# Irradiance_Sensor.net
KiCad netlist of a schematic drawn in Altium Designer
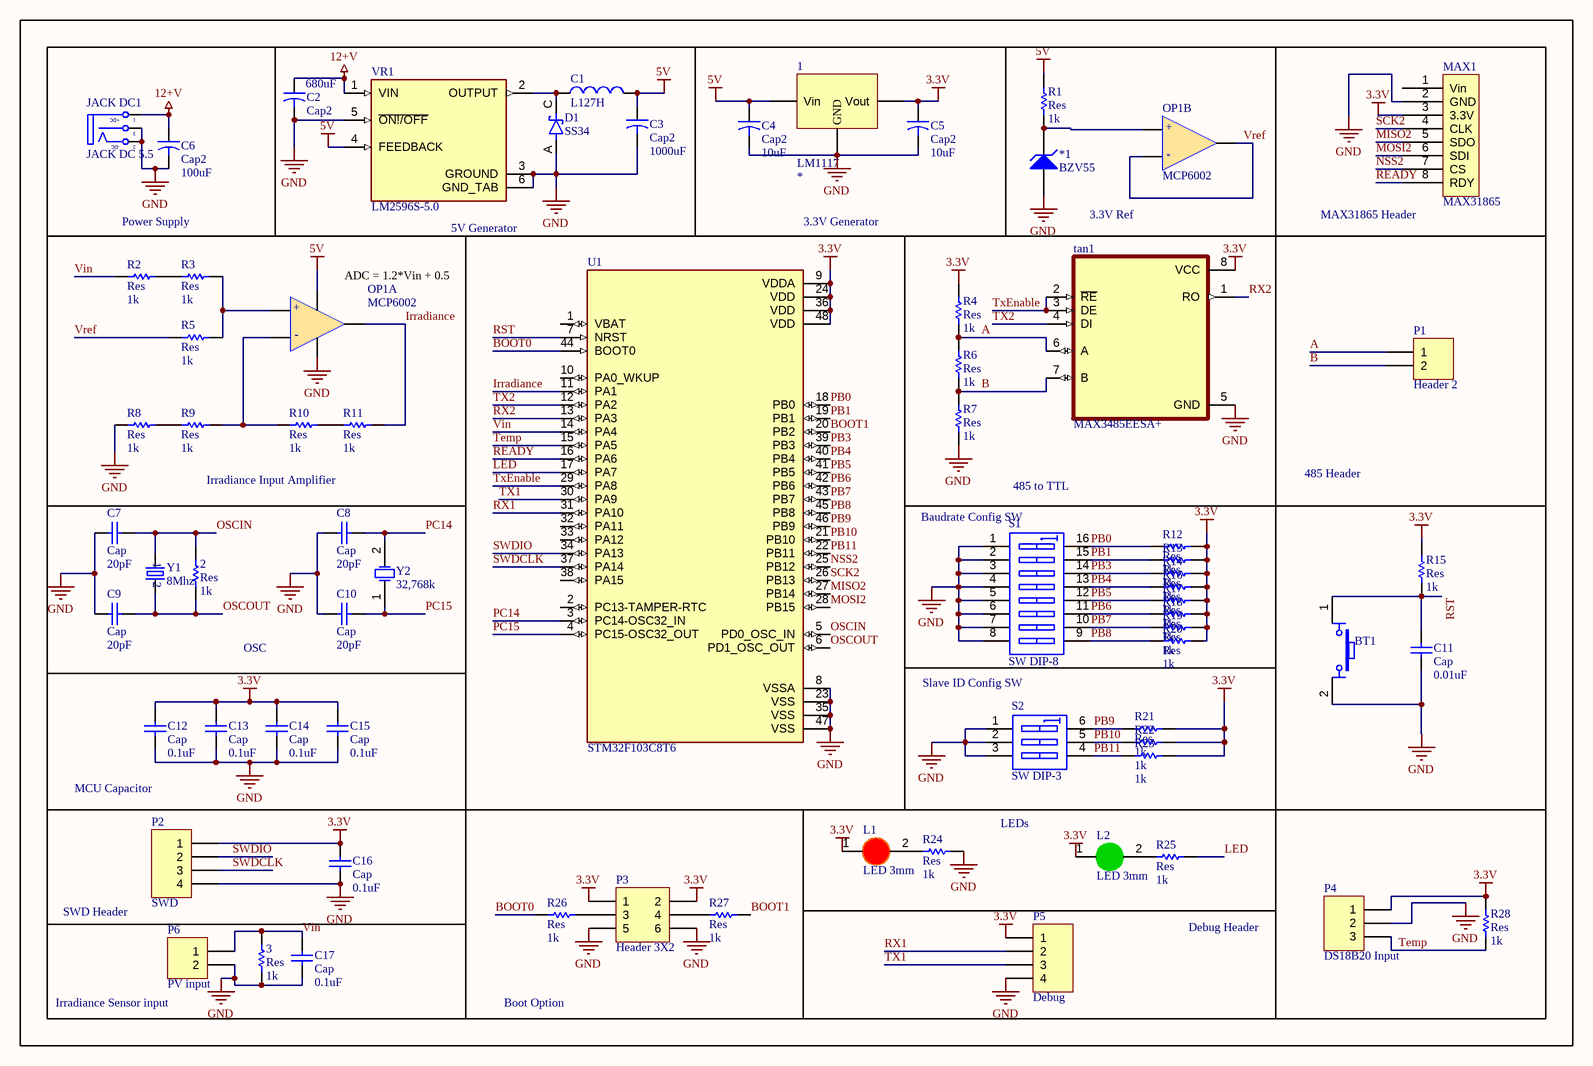
[diagram p0: Irradiance Sensor.SchDoc]

(export (version "E")
  (design (tool "Eeschema 10.0.6"))
  (components
    (comp (ref "*1") (value "BZV55") (footprint "SOD-80C") (libsource (lib "Miles") (part "BZV55")))
    (comp (ref "1")
      (value "LM1117")
      (footprint "SOT230P700X180-4N")
      (fields (field (name "VOLTAGE") "*"))
      (libsource (lib "Miles") (part "LM1117"))
    )
    (comp (ref "2")
      (value "Res")
      (footprint "RESC2012X11N")
      (fields (field (name "ALTIUM_VALUE") "1k"))
      (libsource (lib "Miles") (part "Res"))
    )
    (comp (ref "3")
      (value "Res")
      (footprint "RESC2012X11N")
      (fields (field (name "ALTIUM_VALUE") "1k"))
      (libsource (lib "Miles") (part "Res"))
    )
    (comp (ref "BT1")
      (value "Nut Nhan 4 Chan Cam 6x6")
      (footprint "Nut Nhan 4 Chan Cam 6x6")
      (description "Nut Nhan 4 Chan 6x6mm")
      (libsource (lib "Altium_Lib_by_KhueNguyenCreator") (part "Nut Nhan 4 Chan Cam 6x6"))
    )
    (comp (ref "C1") (value "L127H") (footprint "INDP122122X80N") (libsource (lib "Miles") (part "L127H")))
    (comp (ref "C2")
      (value "Cap2")
      (footprint "CAPR5-4X5")
      (description "Capacitor")
      (fields (field (name "ALTIUM_VALUE") "680uF") (field (name "PUBLISHER") "Altium Limited"))
      (libsource (lib "Miscellaneous Devices") (part "Cap2"))
    )
    (comp (ref "C3")
      (value "Cap2")
      (footprint "CAPR5-4X5")
      (description "Capacitor")
      (fields (field (name "ALTIUM_VALUE") "1000uF") (field (name "PUBLISHER") "Altium Limited"))
      (libsource (lib "Miscellaneous Devices") (part "Cap2"))
    )
    (comp (ref "C4")
      (value "Cap2")
      (footprint "CAPR5-4X5")
      (description "Capacitor")
      (fields (field (name "ALTIUM_VALUE") "10uF") (field (name "PUBLISHER") "Altium Limited"))
      (libsource (lib "Miscellaneous Devices") (part "Cap2"))
    )
    (comp (ref "C5")
      (value "Cap2")
      (footprint "CAPR5-4X5")
      (description "Capacitor")
      (fields (field (name "ALTIUM_VALUE") "10uF") (field (name "PUBLISHER") "Altium Limited"))
      (libsource (lib "Miscellaneous Devices") (part "Cap2"))
    )
    (comp (ref "C6")
      (value "Cap2")
      (footprint "CAPR5-4X5")
      (description "Capacitor")
      (fields (field (name "ALTIUM_VALUE") "100uF") (field (name "PUBLISHER") "Altium Limited"))
      (libsource (lib "Miscellaneous Devices") (part "Cap2"))
    )
    (comp (ref "C7")
      (value "Cap")
      (footprint "RESC2012X11N")
      (fields (field (name "CAP") "20pF"))
      (libsource (lib "Miles") (part "Cap"))
    )
    (comp (ref "C8")
      (value "Cap")
      (footprint "RESC2012X11N")
      (fields (field (name "CAP") "20pF"))
      (libsource (lib "Miles") (part "Cap"))
    )
    (comp (ref "C9")
      (value "Cap")
      (footprint "RESC2012X11N")
      (fields (field (name "CAP") "20pF"))
      (libsource (lib "Miles") (part "Cap"))
    )
    (comp (ref "C10")
      (value "Cap")
      (footprint "RESC2012X11N")
      (fields (field (name "CAP") "20pF"))
      (libsource (lib "Miles") (part "Cap"))
    )
    (comp (ref "C11")
      (value "Cap")
      (footprint "RESC2012X11N")
      (fields (field (name "CAP") "0.01uF"))
      (libsource (lib "Miles") (part "Cap"))
    )
    (comp (ref "C12")
      (value "Cap")
      (footprint "RESC2012X11N")
      (fields (field (name "CAP") "0.1uF"))
      (libsource (lib "Miles") (part "Cap"))
    )
    (comp (ref "C13")
      (value "Cap")
      (footprint "RESC2012X11N")
      (fields (field (name "CAP") "0.1uF"))
      (libsource (lib "Miles") (part "Cap"))
    )
    (comp (ref "C14")
      (value "Cap")
      (footprint "RESC2012X11N")
      (fields (field (name "CAP") "0.1uF"))
      (libsource (lib "Miles") (part "Cap"))
    )
    (comp (ref "C15")
      (value "Cap")
      (footprint "RESC2012X11N")
      (fields (field (name "CAP") "0.1uF"))
      (libsource (lib "Miles") (part "Cap"))
    )
    (comp (ref "C16")
      (value "Cap")
      (footprint "RESC2012X11N")
      (fields (field (name "CAP") "0.1uF"))
      (libsource (lib "Miles") (part "Cap"))
    )
    (comp (ref "C17")
      (value "Cap")
      (footprint "RESC2012X11N")
      (fields (field (name "CAP") "0.1uF"))
      (libsource (lib "Miles") (part "Cap"))
    )
    (comp (ref "D1")
      (value "SS34")
      (footprint "DIOM7959X265N")
      (description "Diode Schottky 40V 3A Surface Mount SMC _DO-214AB_")
      (fields (field (name "MF") "ON Semiconductor"))
      (libsource (lib "SS34") (part "SS34"))
    )
    (comp (ref "JACK DC1")
      (value "JACK DC 5.5")
      (footprint "JACK DC 5.5")
      (libsource (lib "Altium_Lib_by_KhueNguyenCreator") (part "JACK DC 5.5"))
    )
    (comp (ref "L1")
      (value "LED 3mm")
      (footprint "LED-3MM-RED")
      (description "Cắm")
      (libsource (lib "Altium_Lib_by_KhueNguyenCreator") (part "LED 3mm Do"))
    )
    (comp (ref "L2")
      (value "LED 3mm")
      (footprint "LED-3MM-GREEN")
      (description "Cắm")
      (libsource (lib "Altium_Lib_by_KhueNguyenCreator") (part "LED 3mm Xanh La"))
    )
    (comp (ref "MAX1") (value "MAX31865") (footprint "MAX31865") (libsource (lib "Miles") (part "MAX31865")))
    (comp (ref "OP1") (value "MCP6002") (footprint "DIP8") (libsource (lib "Miles") (part "MCP6002")))
    (comp (ref "P1")
      (value "Header 2")
      (footprint "TE_282837-2")
      (description "Header, 2-Pin")
      (fields (field (name "PUBLISHER") "Altium Limited"))
      (libsource (lib "Miscellaneous Connectors") (part "Header 2"))
    )
    (comp (ref "P2")
      (value "SWD")
      (footprint "HDR1X4")
      (description "Header, 4-Pin")
      (fields (field (name "PUBLISHER") "Altium Limited"))
      (libsource (lib "Miscellaneous Connectors") (part "Header 4"))
    )
    (comp (ref "P3")
      (value "Header 3X2")
      (footprint "HDR2X3")
      (description "Header, 3-Pin, Dual row")
      (fields (field (name "PUBLISHER") "Altium Limited"))
      (libsource (lib "Miscellaneous Connectors") (part "Header 3X2"))
    )
    (comp (ref "P4")
      (value "DS18B20 Input")
      (footprint "HDR1X3")
      (description "Header, 3-Pin")
      (fields (field (name "PUBLISHER") "Altium Limited"))
      (libsource (lib "Miscellaneous Connectors") (part "Header 3"))
    )
    (comp (ref "P5")
      (value "Debug")
      (footprint "HDR1X4")
      (description "Header, 4-Pin")
      (fields (field (name "PUBLISHER") "Altium Limited"))
      (libsource (lib "") (part "Header 4_1"))
    )
    (comp (ref "P6")
      (value "PV input")
      (footprint "HDR1X2")
      (description "Header, 2-Pin")
      (fields (field (name "PUBLISHER") "Altium Limited"))
      (libsource (lib "") (part "Header 2_1"))
    )
    (comp (ref "R1")
      (value "Res")
      (footprint "RESC2012X11N")
      (fields (field (name "ALTIUM_VALUE") "1k"))
      (libsource (lib "Miles") (part "Res"))
    )
    (comp (ref "R2")
      (value "Res")
      (footprint "RESC2012X11N")
      (fields (field (name "ALTIUM_VALUE") "1k"))
      (libsource (lib "Miles") (part "Res"))
    )
    (comp (ref "R3")
      (value "Res")
      (footprint "RESC2012X11N")
      (fields (field (name "ALTIUM_VALUE") "1k"))
      (libsource (lib "Miles") (part "Res"))
    )
    (comp (ref "R4")
      (value "Res")
      (footprint "RESC2012X11N")
      (fields (field (name "ALTIUM_VALUE") "1k"))
      (libsource (lib "Miles") (part "Res"))
    )
    (comp (ref "R5")
      (value "Res")
      (footprint "RESC2012X11N")
      (fields (field (name "ALTIUM_VALUE") "1k"))
      (libsource (lib "Miles") (part "Res"))
    )
    (comp (ref "R6")
      (value "Res")
      (footprint "RESC2012X11N")
      (fields (field (name "ALTIUM_VALUE") "1k"))
      (libsource (lib "Miles") (part "Res"))
    )
    (comp (ref "R7")
      (value "Res")
      (footprint "RESC2012X11N")
      (fields (field (name "ALTIUM_VALUE") "1k"))
      (libsource (lib "Miles") (part "Res"))
    )
    (comp (ref "R8")
      (value "Res")
      (footprint "RESC2012X11N")
      (fields (field (name "ALTIUM_VALUE") "1k"))
      (libsource (lib "Miles") (part "Res"))
    )
    (comp (ref "R9")
      (value "Res")
      (footprint "RESC2012X11N")
      (fields (field (name "ALTIUM_VALUE") "1k"))
      (libsource (lib "Miles") (part "Res"))
    )
    (comp (ref "R10")
      (value "Res")
      (footprint "RESC2012X11N")
      (fields (field (name "ALTIUM_VALUE") "1k"))
      (libsource (lib "Miles") (part "Res"))
    )
    (comp (ref "R11")
      (value "Res")
      (footprint "RESC2012X11N")
      (fields (field (name "ALTIUM_VALUE") "1k"))
      (libsource (lib "Miles") (part "Res"))
    )
    (comp (ref "R12")
      (value "Res")
      (footprint "RESC2012X11N")
      (fields (field (name "ALTIUM_VALUE") "1k"))
      (libsource (lib "Miles") (part "Res"))
    )
    (comp (ref "R13")
      (value "Res")
      (footprint "RESC2012X11N")
      (fields (field (name "ALTIUM_VALUE") "1k"))
      (libsource (lib "Miles") (part "Res"))
    )
    (comp (ref "R14")
      (value "Res")
      (footprint "RESC2012X11N")
      (fields (field (name "ALTIUM_VALUE") "1k"))
      (libsource (lib "Miles") (part "Res"))
    )
    (comp (ref "R15")
      (value "Res")
      (footprint "RESC2012X11N")
      (fields (field (name "ALTIUM_VALUE") "1k"))
      (libsource (lib "Miles") (part "Res"))
    )
    (comp (ref "R16")
      (value "Res")
      (footprint "RESC2012X11N")
      (fields (field (name "ALTIUM_VALUE") "1k"))
      (libsource (lib "Miles") (part "Res"))
    )
    (comp (ref "R17")
      (value "Res")
      (footprint "RESC2012X11N")
      (fields (field (name "ALTIUM_VALUE") "1k"))
      (libsource (lib "Miles") (part "Res"))
    )
    (comp (ref "R18")
      (value "Res")
      (footprint "RESC2012X11N")
      (fields (field (name "ALTIUM_VALUE") "1k"))
      (libsource (lib "Miles") (part "Res"))
    )
    (comp (ref "R19")
      (value "Res")
      (footprint "RESC2012X11N")
      (fields (field (name "ALTIUM_VALUE") "1k"))
      (libsource (lib "Miles") (part "Res"))
    )
    (comp (ref "R20")
      (value "Res")
      (footprint "RESC2012X11N")
      (fields (field (name "ALTIUM_VALUE") "1k"))
      (libsource (lib "Miles") (part "Res"))
    )
    (comp (ref "R21")
      (value "Res")
      (footprint "RESC2012X11N")
      (fields (field (name "ALTIUM_VALUE") "1k"))
      (libsource (lib "Miles") (part "Res"))
    )
    (comp (ref "R22") (value "1k") (footprint "RESC2012X11N") (libsource (lib "Miles") (part "Res")))
    (comp (ref "R23") (value "1k") (footprint "RESC2012X11N") (libsource (lib "Miles") (part "Res")))
    (comp (ref "R24")
      (value "Res")
      (footprint "RESC2012X11N")
      (fields (field (name "ALTIUM_VALUE") "1k"))
      (libsource (lib "Miles") (part "Res"))
    )
    (comp (ref "R25")
      (value "Res")
      (footprint "RESC2012X11N")
      (fields (field (name "ALTIUM_VALUE") "1k"))
      (libsource (lib "Miles") (part "Res"))
    )
    (comp (ref "R26")
      (value "Res")
      (footprint "RESC2012X11N")
      (fields (field (name "ALTIUM_VALUE") "1k"))
      (libsource (lib "Miles") (part "Res"))
    )
    (comp (ref "R27")
      (value "Res")
      (footprint "RESC2012X11N")
      (fields (field (name "ALTIUM_VALUE") "1k"))
      (libsource (lib "Miles") (part "Res"))
    )
    (comp (ref "R28")
      (value "Res")
      (footprint "RESC2012X11N")
      (fields (field (name "ALTIUM_VALUE") "1k"))
      (libsource (lib "Miles") (part "Res"))
    )
    (comp (ref "S1")
      (value "SW DIP-8")
      (footprint "DIP16")
      (description "DIP Switch, 8 Position, SPST")
      (fields (field (name "PUBLISHER") "Altium Limited"))
      (libsource (lib "Miscellaneous Devices") (part "SW DIP-8"))
    )
    (comp (ref "S2")
      (value "SW DIP-3")
      (footprint "DIP-6")
      (description "DIP Switch, 3 Position, SPST")
      (fields (field (name "PUBLISHER") "Altium Limited"))
      (libsource (lib "Miscellaneous Devices") (part "SW DIP-3"))
    )
    (comp (ref "tan1")
      (value "MAX3485EESA+")
      (footprint "SOIC127P600X175-8N")
      (description "1/1 Transceiver Half RS422, RS485 8-SOIC")
      (fields (field (name "MF") "Maxim Integrated"))
      (libsource (lib "MAX3485EESA_") (part "MAX3485EESA+"))
    )
    (comp (ref "U1")
      (value "STM32F103C8T6")
      (footprint "QFP50P900X900X160-48N")
      (description "ARMÂ® CortexÂ®-M3 STM32F1 Microcontroller IC 32-Bit 72MHz 64KB _64K x 8_ FLASH")
      (fields (field (name "MF") "STMicroelectronics"))
      (libsource (lib "STM32F103C8T6") (part "STM32F103C8T6"))
    )
    (comp (ref "VR1")
      (value "LM2596S-5.0")
      (footprint "TO170P1524X483-6N")
      (description "SIMPLE SWITCHER&reg; 4.5V to 40V, 3A Low Component Count Step-Down Regulator 5-DDPAK/TO-263")
      (fields (field (name "MF") "Texas Instruments") (field (name "MP") "LM2596S-5.0/NOPB"))
      (libsource (lib "LM2596S-5.0") (part "LM2596S-5.0"))
    )
    (comp (ref "Y1")
      (value "8Mhz")
      (footprint "HC49US")
      (description "DIP Crystal 8MHz-20pF-20ppm-60R;")
      (fields (field (name "MF") "Xinhunjing") (field (name "MP") "49S8M"))
      (libsource (lib "DIP-CRYSTAL-8MHZ-20PF-20PPM-60R_HC49US_") (part "DIP-CRYSTAL-8MHZ-20PF-20PPM-60R(HC49US)"))
    )
    (comp (ref "Y2")
      (value "32,768k")
      (footprint "R38")
      (description "Crystal Oscillator")
      (fields (field (name "PUBLISHER") "Altium Limited"))
      (libsource (lib "Miscellaneous Devices") (part "XTAL"))
    )
  )
  (nets
    (net (code "1") (name "/A") (class "Default")
      (node (ref "P1") (pin "1") (pinfunction "1_1") (pintype "passive"))
      (node (ref "R4") (pin "1") (pinfunction "1_1") (pintype "passive"))
      (node (ref "R6") (pin "2") (pinfunction "2_2") (pintype "passive"))
      (node (ref "tan1") (pin "6") (pinfunction "A_6") (pintype "bidirectional"))
    )
    (net (code "2") (name "/B") (class "Default")
      (node (ref "P1") (pin "2") (pinfunction "2_2") (pintype "passive"))
      (node (ref "R6") (pin "1") (pinfunction "1_1") (pintype "passive"))
      (node (ref "R7") (pin "2") (pinfunction "2_2") (pintype "passive"))
      (node (ref "tan1") (pin "7") (pinfunction "B_7") (pintype "bidirectional"))
    )
    (net (code "3") (name "/BOOT0") (class "Default")
      (node (ref "R26") (pin "2") (pinfunction "2_2") (pintype "passive"))
      (node (ref "U1") (pin "44") (pinfunction "BOOT0_44") (pintype "input"))
    )
    (net (code "4") (name "/BOOT1") (class "Default")
      (node (ref "R27") (pin "1") (pinfunction "1_1") (pintype "passive"))
      (node (ref "U1") (pin "20") (pinfunction "PB2_20") (pintype "bidirectional"))
    )
    (net (code "5") (name "/Irradiance") (class "Default")
      (node (ref "OP1") (pin "1") (pinfunction "VoutA_1") (pintype "passive"))
      (node (ref "R11") (pin "2") (pinfunction "2_2") (pintype "passive"))
      (node (ref "U1") (pin "11") (pinfunction "PA1_11") (pintype "bidirectional"))
    )
    (net (code "6") (name "/LED") (class "Default")
      (node (ref "R25") (pin "1") (pinfunction "1_1") (pintype "passive"))
      (node (ref "U1") (pin "17") (pinfunction "PA7_17") (pintype "bidirectional"))
    )
    (net (code "7") (name "/MISO2") (class "Default")
      (node (ref "MAX1") (pin "5") (pinfunction "SDO_5") (pintype "passive"))
      (node (ref "U1") (pin "27") (pinfunction "PB14_27") (pintype "bidirectional"))
    )
    (net (code "8") (name "/MOSI2") (class "Default")
      (node (ref "MAX1") (pin "6") (pinfunction "SDI_6") (pintype "passive"))
      (node (ref "U1") (pin "28") (pinfunction "PB15_28") (pintype "bidirectional"))
    )
    (net (code "9") (name "/NSS2") (class "Default")
      (node (ref "MAX1") (pin "7") (pinfunction "CS_7") (pintype "passive"))
      (node (ref "U1") (pin "25") (pinfunction "PB12_25") (pintype "bidirectional"))
    )
    (net (code "10") (name "/OSCIN") (class "Default")
      (node (ref "2") (pin "2") (pinfunction "2_2") (pintype "passive"))
      (node (ref "C7") (pin "2") (pinfunction "2_2") (pintype "passive"))
      (node (ref "U1") (pin "5") (pinfunction "PD0_OSC_IN_5") (pintype "bidirectional"))
      (node (ref "Y1") (pin "1") (pinfunction "1_1") (pintype "passive"))
    )
    (net (code "11") (name "/OSCOUT") (class "Default")
      (node (ref "2") (pin "1") (pinfunction "1_1") (pintype "passive"))
      (node (ref "C9") (pin "2") (pinfunction "2_2") (pintype "passive"))
      (node (ref "U1") (pin "6") (pinfunction "PD1_OSC_OUT_6") (pintype "bidirectional"))
      (node (ref "Y1") (pin "2") (pinfunction "2_2") (pintype "passive"))
    )
    (net (code "12") (name "/PB0") (class "Default")
      (node (ref "R12") (pin "2") (pinfunction "2_2") (pintype "passive"))
      (node (ref "S1") (pin "16") (pinfunction "B1_16") (pintype "passive"))
      (node (ref "U1") (pin "18") (pinfunction "PB0_18") (pintype "bidirectional"))
    )
    (net (code "13") (name "/PB1") (class "Default")
      (node (ref "R13") (pin "2") (pinfunction "2_2") (pintype "passive"))
      (node (ref "S1") (pin "15") (pinfunction "B2_15") (pintype "passive"))
      (node (ref "U1") (pin "19") (pinfunction "PB1_19") (pintype "bidirectional"))
    )
    (net (code "14") (name "/PB3") (class "Default")
      (node (ref "R14") (pin "2") (pinfunction "2_2") (pintype "passive"))
      (node (ref "S1") (pin "14") (pinfunction "B3_14") (pintype "passive"))
      (node (ref "U1") (pin "39") (pinfunction "PB3_39") (pintype "bidirectional"))
    )
    (net (code "15") (name "/PB4") (class "Default")
      (node (ref "R16") (pin "2") (pinfunction "2_2") (pintype "passive"))
      (node (ref "S1") (pin "13") (pinfunction "B4_13") (pintype "passive"))
      (node (ref "U1") (pin "40") (pinfunction "PB4_40") (pintype "bidirectional"))
    )
    (net (code "16") (name "/PB5") (class "Default")
      (node (ref "R17") (pin "2") (pinfunction "2_2") (pintype "passive"))
      (node (ref "S1") (pin "12") (pinfunction "B5_12") (pintype "passive"))
      (node (ref "U1") (pin "41") (pinfunction "PB5_41") (pintype "bidirectional"))
    )
    (net (code "17") (name "/PB6") (class "Default")
      (node (ref "R18") (pin "2") (pinfunction "2_2") (pintype "passive"))
      (node (ref "S1") (pin "11") (pinfunction "B6_11") (pintype "passive"))
      (node (ref "U1") (pin "42") (pinfunction "PB6_42") (pintype "bidirectional"))
    )
    (net (code "18") (name "/PB7") (class "Default")
      (node (ref "R19") (pin "2") (pinfunction "2_2") (pintype "passive"))
      (node (ref "S1") (pin "10") (pinfunction "B7_10") (pintype "passive"))
      (node (ref "U1") (pin "43") (pinfunction "PB7_43") (pintype "bidirectional"))
    )
    (net (code "19") (name "/PB8") (class "Default")
      (node (ref "R20") (pin "2") (pinfunction "2_2") (pintype "passive"))
      (node (ref "S1") (pin "9") (pinfunction "B8_9") (pintype "passive"))
      (node (ref "U1") (pin "45") (pinfunction "PB8_45") (pintype "bidirectional"))
    )
    (net (code "20") (name "/PB9") (class "Default")
      (node (ref "R21") (pin "2") (pinfunction "2_2") (pintype "passive"))
      (node (ref "S2") (pin "6") (pinfunction "B1_6") (pintype "passive"))
      (node (ref "U1") (pin "46") (pinfunction "PB9_46") (pintype "bidirectional"))
    )
    (net (code "21") (name "/PB10") (class "Default")
      (node (ref "R22") (pin "2") (pinfunction "2_2") (pintype "passive"))
      (node (ref "S2") (pin "5") (pinfunction "B2_5") (pintype "passive"))
      (node (ref "U1") (pin "21") (pinfunction "PB10_21") (pintype "bidirectional"))
    )
    (net (code "22") (name "/PB11") (class "Default")
      (node (ref "R23") (pin "2") (pinfunction "2_2") (pintype "passive"))
      (node (ref "S2") (pin "4") (pinfunction "B3_4") (pintype "passive"))
      (node (ref "U1") (pin "22") (pinfunction "PB11_22") (pintype "bidirectional"))
    )
    (net (code "23") (name "/PC14") (class "Default")
      (node (ref "C8") (pin "2") (pinfunction "2_2") (pintype "passive"))
      (node (ref "U1") (pin "3") (pinfunction "PC14-OSC32_IN_3") (pintype "bidirectional"))
      (node (ref "Y2") (pin "2") (pinfunction "OSC2_2") (pintype "passive"))
    )
    (net (code "24") (name "/PC15") (class "Default")
      (node (ref "C10") (pin "2") (pinfunction "2_2") (pintype "passive"))
      (node (ref "U1") (pin "4") (pinfunction "PC15-OSC32_OUT_4") (pintype "bidirectional"))
      (node (ref "Y2") (pin "1") (pinfunction "OSC1_1") (pintype "passive"))
    )
    (net (code "25") (name "/READY") (class "Default")
      (node (ref "MAX1") (pin "8") (pinfunction "RDY_8") (pintype "passive"))
      (node (ref "U1") (pin "16") (pinfunction "PA6_16") (pintype "bidirectional"))
    )
    (net (code "26") (name "/RST") (class "Default")
      (node (ref "BT1") (pin "1") (pintype "passive"))
      (node (ref "C11") (pin "1") (pinfunction "1_1") (pintype "passive"))
      (node (ref "R15") (pin "1") (pinfunction "1_1") (pintype "passive"))
      (node (ref "U1") (pin "7") (pinfunction "NRST_7") (pintype "input"))
    )
    (net (code "27") (name "/RX1") (class "Default")
      (node (ref "P5") (pin "2") (pinfunction "2_2") (pintype "passive"))
      (node (ref "U1") (pin "31") (pinfunction "PA10_31") (pintype "bidirectional"))
    )
    (net (code "28") (name "/RX2") (class "Default")
      (node (ref "U1") (pin "13") (pinfunction "PA3_13") (pintype "bidirectional"))
      (node (ref "tan1") (pin "1") (pinfunction "RO_1") (pintype "output"))
    )
    (net (code "29") (name "/SCK2") (class "Default")
      (node (ref "MAX1") (pin "4") (pinfunction "CLK_4") (pintype "passive"))
      (node (ref "U1") (pin "26") (pinfunction "PB13_26") (pintype "bidirectional"))
    )
    (net (code "30") (name "/SWDCLK") (class "Default")
      (node (ref "P2") (pin "3") (pinfunction "3_3") (pintype "passive"))
      (node (ref "U1") (pin "37") (pinfunction "PA14_37") (pintype "bidirectional"))
    )
    (net (code "31") (name "/SWDIO") (class "Default")
      (node (ref "P2") (pin "2") (pinfunction "2_2") (pintype "passive"))
      (node (ref "U1") (pin "34") (pinfunction "PA13_34") (pintype "bidirectional"))
    )
    (net (code "32") (name "/TX1") (class "Default")
      (node (ref "P5") (pin "3") (pinfunction "3_3") (pintype "passive"))
      (node (ref "U1") (pin "30") (pinfunction "PA9_30") (pintype "bidirectional"))
    )
    (net (code "33") (name "/TX2") (class "Default")
      (node (ref "U1") (pin "12") (pinfunction "PA2_12") (pintype "bidirectional"))
      (node (ref "tan1") (pin "4") (pinfunction "DI_4") (pintype "input"))
    )
    (net (code "34") (name "/Temp") (class "Default")
      (node (ref "P4") (pin "3") (pinfunction "3_3") (pintype "passive"))
      (node (ref "R28") (pin "1") (pinfunction "1_1") (pintype "passive"))
      (node (ref "U1") (pin "15") (pinfunction "PA5_15") (pintype "bidirectional"))
    )
    (net (code "35") (name "/TxEnable") (class "Default")
      (node (ref "U1") (pin "29") (pinfunction "PA8_29") (pintype "bidirectional"))
      (node (ref "tan1") (pin "2") (pinfunction "~{RE}_2") (pintype "input"))
      (node (ref "tan1") (pin "3") (pinfunction "DE_3") (pintype "input"))
    )
    (net (code "36") (name "/Vin") (class "Default")
      (node (ref "3") (pin "2") (pinfunction "2_2") (pintype "passive"))
      (node (ref "C17") (pin "1") (pinfunction "1_1") (pintype "passive"))
      (node (ref "P6") (pin "1") (pinfunction "1_1") (pintype "passive"))
      (node (ref "R2") (pin "1") (pinfunction "1_1") (pintype "passive"))
      (node (ref "U1") (pin "14") (pinfunction "PA4_14") (pintype "bidirectional"))
    )
    (net (code "37") (name "/Vref") (class "Default")
      (node (ref "OP1") (pin "6") (pinfunction "Vinb-_6") (pintype "passive"))
      (node (ref "OP1") (pin "7") (pinfunction "VoutB_7") (pintype "passive"))
      (node (ref "R5") (pin "1") (pinfunction "1_1") (pintype "passive"))
    )
    (net (code "38") (name "3.3V") (class "Default")
      (node (ref "1") (pin "2") (pinfunction "Vout_2") (pintype "passive"))
      (node (ref "C12") (pin "1") (pinfunction "1_1") (pintype "passive"))
      (node (ref "C13") (pin "1") (pinfunction "1_1") (pintype "passive"))
      (node (ref "C14") (pin "1") (pinfunction "1_1") (pintype "passive"))
      (node (ref "C15") (pin "1") (pinfunction "1_1") (pintype "passive"))
      (node (ref "C16") (pin "1") (pinfunction "1_1") (pintype "passive"))
      (node (ref "C5") (pin "1") (pinfunction "1_1") (pintype "passive"))
      (node (ref "L1") (pin "1") (pinfunction "A_1") (pintype "passive"))
      (node (ref "L2") (pin "1") (pinfunction "A_1") (pintype "passive"))
      (node (ref "MAX1") (pin "3") (pinfunction "3.3V_3") (pintype "passive"))
      (node (ref "P2") (pin "1") (pinfunction "1_1") (pintype "passive"))
      (node (ref "P3") (pin "1") (pinfunction "1_1") (pintype "passive"))
      (node (ref "P3") (pin "2") (pinfunction "2_2") (pintype "passive"))
      (node (ref "P4") (pin "1") (pinfunction "1_1") (pintype "passive"))
      (node (ref "P5") (pin "1") (pinfunction "1_1") (pintype "passive"))
      (node (ref "R12") (pin "1") (pinfunction "1_1") (pintype "passive"))
      (node (ref "R13") (pin "1") (pinfunction "1_1") (pintype "passive"))
      (node (ref "R14") (pin "1") (pinfunction "1_1") (pintype "passive"))
      (node (ref "R15") (pin "2") (pinfunction "2_2") (pintype "passive"))
      (node (ref "R16") (pin "1") (pinfunction "1_1") (pintype "passive"))
      (node (ref "R17") (pin "1") (pinfunction "1_1") (pintype "passive"))
      (node (ref "R18") (pin "1") (pinfunction "1_1") (pintype "passive"))
      (node (ref "R19") (pin "1") (pinfunction "1_1") (pintype "passive"))
      (node (ref "R20") (pin "1") (pinfunction "1_1") (pintype "passive"))
      (node (ref "R21") (pin "1") (pinfunction "1_1") (pintype "passive"))
      (node (ref "R22") (pin "1") (pinfunction "1_1") (pintype "passive"))
      (node (ref "R23") (pin "1") (pinfunction "1_1") (pintype "passive"))
      (node (ref "R28") (pin "2") (pinfunction "2_2") (pintype "passive"))
      (node (ref "R4") (pin "2") (pinfunction "2_2") (pintype "passive"))
      (node (ref "U1") (pin "24") (pinfunction "VDD_24") (pintype "power_in"))
      (node (ref "U1") (pin "36") (pinfunction "VDD_36") (pintype "power_in"))
      (node (ref "U1") (pin "48") (pinfunction "VDD_48") (pintype "power_in"))
      (node (ref "U1") (pin "9") (pinfunction "VDDA_9") (pintype "power_in"))
      (node (ref "tan1") (pin "8") (pinfunction "VCC_8") (pintype "power_in"))
    )
    (net (code "39") (name "5V") (class "Default")
      (node (ref "1") (pin "3") (pinfunction "Vin_3") (pintype "passive"))
      (node (ref "C1") (pin "2") (pinfunction "2_2") (pintype "passive"))
      (node (ref "C3") (pin "1") (pinfunction "1_1") (pintype "passive"))
      (node (ref "C4") (pin "1") (pinfunction "1_1") (pintype "passive"))
      (node (ref "OP1") (pin "8") (pinfunction "Vdd_8") (pintype "passive"))
      (node (ref "R1") (pin "2") (pinfunction "2_2") (pintype "passive"))
      (node (ref "VR1") (pin "4") (pinfunction "FEEDBACK_4") (pintype "input"))
    )
    (net (code "40") (name "12+V") (class "Default")
      (node (ref "C2") (pin "1") (pinfunction "1_1") (pintype "passive"))
      (node (ref "C6") (pin "1") (pinfunction "1_1") (pintype "passive"))
      (node (ref "JACK DC1") (pin "1") (pinfunction "T_1") (pintype "passive"))
      (node (ref "VR1") (pin "1") (pinfunction "VIN_1") (pintype "input"))
    )
    (net (code "41") (name "GND") (class "Default")
      (node (ref "*1") (pin "2") (pinfunction "A_2") (pintype "passive"))
      (node (ref "1") (pin "1") (pinfunction "GND_1") (pintype "passive"))
      (node (ref "3") (pin "1") (pinfunction "1_1") (pintype "passive"))
      (node (ref "BT1") (pin "2") (pintype "passive"))
      (node (ref "C10") (pin "1") (pinfunction "1_1") (pintype "passive"))
      (node (ref "C11") (pin "2") (pinfunction "2_2") (pintype "passive"))
      (node (ref "C12") (pin "2") (pinfunction "2_2") (pintype "passive"))
      (node (ref "C13") (pin "2") (pinfunction "2_2") (pintype "passive"))
      (node (ref "C14") (pin "2") (pinfunction "2_2") (pintype "passive"))
      (node (ref "C15") (pin "2") (pinfunction "2_2") (pintype "passive"))
      (node (ref "C16") (pin "2") (pinfunction "2_2") (pintype "passive"))
      (node (ref "C17") (pin "2") (pinfunction "2_2") (pintype "passive"))
      (node (ref "C2") (pin "2") (pinfunction "2_2") (pintype "passive"))
      (node (ref "C3") (pin "2") (pinfunction "2_2") (pintype "passive"))
      (node (ref "C4") (pin "2") (pinfunction "2_2") (pintype "passive"))
      (node (ref "C5") (pin "2") (pinfunction "2_2") (pintype "passive"))
      (node (ref "C6") (pin "2") (pinfunction "2_2") (pintype "passive"))
      (node (ref "C7") (pin "1") (pinfunction "1_1") (pintype "passive"))
      (node (ref "C8") (pin "1") (pinfunction "1_1") (pintype "passive"))
      (node (ref "C9") (pin "1") (pinfunction "1_1") (pintype "passive"))
      (node (ref "D1") (pin "A") (pinfunction "A_A") (pintype "passive"))
      (node (ref "JACK DC1") (pin "2") (pinfunction "TN_2") (pintype "passive"))
      (node (ref "JACK DC1") (pin "3") (pinfunction "S_3") (pintype "power_in"))
      (node (ref "MAX1") (pin "2") (pinfunction "GND_2") (pintype "passive"))
      (node (ref "OP1") (pin "4") (pinfunction "Vss_4") (pintype "passive"))
      (node (ref "P2") (pin "4") (pinfunction "4_4") (pintype "passive"))
      (node (ref "P3") (pin "5") (pinfunction "5_5") (pintype "passive"))
      (node (ref "P3") (pin "6") (pinfunction "6_6") (pintype "passive"))
      (node (ref "P4") (pin "2") (pinfunction "2_2") (pintype "passive"))
      (node (ref "P5") (pin "4") (pinfunction "4_4") (pintype "passive"))
      (node (ref "P6") (pin "2") (pinfunction "2_2") (pintype "passive"))
      (node (ref "R24") (pin "1") (pinfunction "1_1") (pintype "passive"))
      (node (ref "R7") (pin "1") (pinfunction "1_1") (pintype "passive"))
      (node (ref "R8") (pin "1") (pinfunction "1_1") (pintype "passive"))
      (node (ref "S1") (pin "1") (pinfunction "A1_1") (pintype "passive"))
      (node (ref "S1") (pin "2") (pinfunction "A2_2") (pintype "passive"))
      (node (ref "S1") (pin "3") (pinfunction "A3_3") (pintype "passive"))
      (node (ref "S1") (pin "4") (pinfunction "A4_4") (pintype "passive"))
      (node (ref "S1") (pin "5") (pinfunction "A5_5") (pintype "passive"))
      (node (ref "S1") (pin "6") (pinfunction "A6_6") (pintype "passive"))
      (node (ref "S1") (pin "7") (pinfunction "A7_7") (pintype "passive"))
      (node (ref "S1") (pin "8") (pinfunction "A8_8") (pintype "passive"))
      (node (ref "S2") (pin "1") (pinfunction "A1_1") (pintype "passive"))
      (node (ref "S2") (pin "2") (pinfunction "A2_2") (pintype "passive"))
      (node (ref "S2") (pin "3") (pinfunction "A3_3") (pintype "passive"))
      (node (ref "U1") (pin "23") (pinfunction "VSS_23") (pintype "power_in"))
      (node (ref "U1") (pin "35") (pinfunction "VSS_35") (pintype "power_in"))
      (node (ref "U1") (pin "47") (pinfunction "VSS_47") (pintype "power_in"))
      (node (ref "U1") (pin "8") (pinfunction "VSSA_8") (pintype "power_in"))
      (node (ref "VR1") (pin "3") (pinfunction "GROUND_3") (pintype "power_in"))
      (node (ref "VR1") (pin "5") (pinfunction "~{ON!/OFF}_5") (pintype "input"))
      (node (ref "VR1") (pin "6") (pinfunction "GND_TAB_6") (pintype "power_in"))
      (node (ref "tan1") (pin "5") (pinfunction "GND_5") (pintype "power_in"))
    )
    (net (code "42") (name "Net-(*1-K)") (class "Default")
      (node (ref "*1") (pin "1") (pinfunction "K_1") (pintype "passive"))
      (node (ref "OP1") (pin "5") (pinfunction "Vinb+_5") (pintype "passive"))
      (node (ref "R1") (pin "1") (pinfunction "1_1") (pintype "passive"))
    )
    (net (code "43") (name "Net-(D1-K)") (class "Default")
      (node (ref "C1") (pin "1") (pinfunction "1_1") (pintype "passive"))
      (node (ref "D1") (pin "C") (pinfunction "K_C") (pintype "passive"))
      (node (ref "VR1") (pin "2") (pinfunction "OUTPUT_2") (pintype "output"))
    )
    (net (code "44") (name "Net-(L1-K)") (class "Default")
      (node (ref "L1") (pin "2") (pinfunction "K_2") (pintype "passive"))
      (node (ref "R24") (pin "2") (pinfunction "2_2") (pintype "passive"))
    )
    (net (code "45") (name "Net-(L2-K)") (class "Default")
      (node (ref "L2") (pin "2") (pinfunction "K_2") (pintype "passive"))
      (node (ref "R25") (pin "2") (pinfunction "2_2") (pintype "passive"))
    )
    (net (code "46") (name "Net-(OP1A-Vina+)") (class "Default")
      (node (ref "OP1") (pin "3") (pinfunction "Vina+_3") (pintype "passive"))
      (node (ref "R3") (pin "2") (pinfunction "2_2") (pintype "passive"))
      (node (ref "R5") (pin "2") (pinfunction "2_2") (pintype "passive"))
    )
    (net (code "47") (name "Net-(OP1A-Vina-)") (class "Default")
      (node (ref "OP1") (pin "2") (pinfunction "Vina-_2") (pintype "passive"))
      (node (ref "R10") (pin "1") (pinfunction "1_1") (pintype "passive"))
      (node (ref "R9") (pin "2") (pinfunction "2_2") (pintype "passive"))
    )
    (net (code "48") (name "Net-(P3-Pad3)") (class "Default")
      (node (ref "P3") (pin "3") (pinfunction "3_3") (pintype "passive"))
      (node (ref "R26") (pin "1") (pinfunction "1_1") (pintype "passive"))
    )
    (net (code "49") (name "Net-(P3-Pad4)") (class "Default")
      (node (ref "P3") (pin "4") (pinfunction "4_4") (pintype "passive"))
      (node (ref "R27") (pin "2") (pinfunction "2_2") (pintype "passive"))
    )
    (net (code "50") (name "Net-(R2-Pad2)") (class "Default")
      (node (ref "R2") (pin "2") (pinfunction "2_2") (pintype "passive"))
      (node (ref "R3") (pin "1") (pinfunction "1_1") (pintype "passive"))
    )
    (net (code "51") (name "Net-(R8-Pad2)") (class "Default")
      (node (ref "R8") (pin "2") (pinfunction "2_2") (pintype "passive"))
      (node (ref "R9") (pin "1") (pinfunction "1_1") (pintype "passive"))
    )
    (net (code "52") (name "Net-(R10-Pad2)") (class "Default")
      (node (ref "R10") (pin "2") (pinfunction "2_2") (pintype "passive"))
      (node (ref "R11") (pin "1") (pinfunction "1_1") (pintype "passive"))
    )
    (net (code "53") (name "unconnected-(MAX1-Vin-Pad1)") (class "Default")
      (node (ref "MAX1") (pin "1") (pinfunction "Vin_1") (pintype "passive"))
    )
    (net (code "54") (name "unconnected-(U1-PA0_WKUP-Pad10)") (class "Default")
      (node (ref "U1") (pin "10") (pinfunction "PA0_WKUP_10") (pintype "bidirectional"))
    )
    (net (code "55") (name "unconnected-(U1-PA11-Pad32)") (class "Default")
      (node (ref "U1") (pin "32") (pinfunction "PA11_32") (pintype "bidirectional"))
    )
    (net (code "56") (name "unconnected-(U1-PA12-Pad33)") (class "Default")
      (node (ref "U1") (pin "33") (pinfunction "PA12_33") (pintype "bidirectional"))
    )
    (net (code "57") (name "unconnected-(U1-PA15-Pad38)") (class "Default")
      (node (ref "U1") (pin "38") (pinfunction "PA15_38") (pintype "bidirectional"))
    )
    (net (code "58") (name "unconnected-(U1-PC13-TAMPER-RTC-Pad2)") (class "Default")
      (node (ref "U1") (pin "2") (pinfunction "PC13-TAMPER-RTC_2") (pintype "bidirectional"))
    )
    (net (code "59") (name "unconnected-(U1-VBAT-Pad1)") (class "Default")
      (node (ref "U1") (pin "1") (pinfunction "VBAT_1") (pintype "bidirectional"))
    )
  )
)
